# pcbNoJet.net
KiCad netlist of a schematic drawn in EAGLE
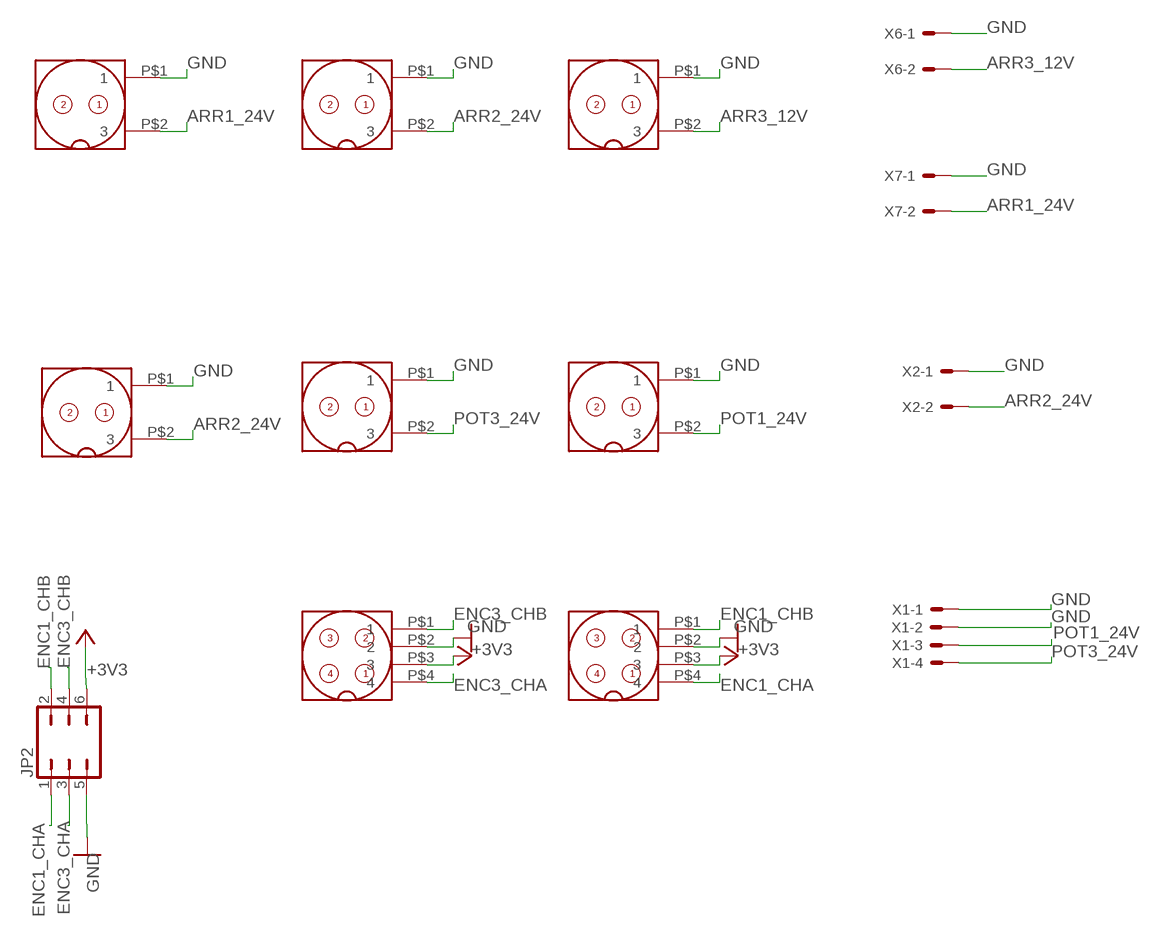
[diagram p0: schematic, sheet 1]

(export (version "E")
  (design (tool "Eeschema 10.0.6"))
  (components
    (comp (ref "JP2")
      (value "JP3Q")
      (footprint "eagle-import:JP3Q")
      (libsource (lib "eagle-import") (part "JP3Q"))
    )
    (comp (ref "U$1")
      (value "GX16_2_PINS")
      (footprint "eagle-import:GX16_2_PINS_PADS")
      (libsource (lib "eagle-import") (part "GX16_2_PINS"))
    )
    (comp (ref "U$2")
      (value "GX16_4_PINS")
      (footprint "eagle-import:GX16_4_PINS_PADS")
      (libsource (lib "eagle-import") (part "GX16_4_PINS"))
    )
    (comp (ref "U$3")
      (value "GX16_4_PINS")
      (footprint "eagle-import:GX16_4_PINS_PADS")
      (libsource (lib "eagle-import") (part "GX16_4_PINS"))
    )
    (comp (ref "U$4")
      (value "GX16_2_PINS")
      (footprint "eagle-import:GX16_2_PINS_PADS")
      (libsource (lib "eagle-import") (part "GX16_2_PINS"))
    )
    (comp (ref "U$5")
      (value "GX16_2_PINS")
      (footprint "eagle-import:GX16_2_PINS_PADS")
      (libsource (lib "eagle-import") (part "GX16_2_PINS"))
    )
    (comp (ref "U$6")
      (value "GX16_2_PINS")
      (footprint "eagle-import:GX16_2_PINS_PADS")
      (libsource (lib "eagle-import") (part "GX16_2_PINS"))
    )
    (comp (ref "U$8")
      (value "GX16_2_PINS")
      (footprint "eagle-import:GX16_2_PINS_PADS")
      (libsource (lib "eagle-import") (part "GX16_2_PINS"))
    )
    (comp (ref "U$9")
      (value "GX16_2_PINS")
      (footprint "eagle-import:GX16_2_PINS_PADS")
      (libsource (lib "eagle-import") (part "GX16_2_PINS"))
    )
    (comp (ref "X1")
      (value "5566-45569-4")
      (footprint "eagle-import:5569-4")
      (libsource (lib "eagle-import") (part "5566-45569-4"))
    )
    (comp (ref "X2")
      (value "5566-25569-2")
      (footprint "eagle-import:5569-2")
      (libsource (lib "eagle-import") (part "5566-25569-2"))
    )
    (comp (ref "X6")
      (value "5566-25569-2")
      (footprint "eagle-import:5569-2")
      (libsource (lib "eagle-import") (part "5566-25569-2"))
    )
    (comp (ref "X7")
      (value "5566-25569-2")
      (footprint "eagle-import:5569-2")
      (libsource (lib "eagle-import") (part "5566-25569-2"))
    )
  )
  (nets
    (net (code "1") (name "+3V3") (class "Default")
      (node (ref "JP2") (pin "6") (pinfunction "6_6") (pintype "passive"))
      (node (ref "U$2") (pin "P$3") (pinfunction "3_P$3") (pintype "bidirectional"))
      (node (ref "U$3") (pin "P$3") (pinfunction "3_P$3") (pintype "bidirectional"))
    )
    (net (code "2") (name "/ARR1_24V") (class "Default")
      (node (ref "U$4") (pin "P$2") (pinfunction "3_P$2") (pintype "bidirectional"))
      (node (ref "X7") (pin "2") (pinfunction "S_2") (pintype "passive"))
    )
    (net (code "3") (name "/ARR2_24V") (class "Default")
      (node (ref "U$1") (pin "P$2") (pinfunction "3_P$2") (pintype "bidirectional"))
      (node (ref "U$5") (pin "P$2") (pinfunction "3_P$2") (pintype "bidirectional"))
      (node (ref "X2") (pin "2") (pinfunction "S_2") (pintype "passive"))
    )
    (net (code "4") (name "/ARR3_12V") (class "Default")
      (node (ref "U$6") (pin "P$2") (pinfunction "3_P$2") (pintype "bidirectional"))
      (node (ref "X6") (pin "2") (pinfunction "S_2") (pintype "passive"))
    )
    (net (code "5") (name "/ENC1_CHA") (class "Default")
      (node (ref "JP2") (pin "1") (pinfunction "1_1") (pintype "passive"))
      (node (ref "U$3") (pin "P$4") (pinfunction "4_P$4") (pintype "bidirectional"))
    )
    (net (code "6") (name "/ENC1_CHB") (class "Default")
      (node (ref "JP2") (pin "2") (pinfunction "2_2") (pintype "passive"))
      (node (ref "U$3") (pin "P$1") (pinfunction "1_P$1") (pintype "bidirectional"))
    )
    (net (code "7") (name "/ENC3_CHA") (class "Default")
      (node (ref "JP2") (pin "3") (pinfunction "3_3") (pintype "passive"))
      (node (ref "U$2") (pin "P$4") (pinfunction "4_P$4") (pintype "bidirectional"))
    )
    (net (code "8") (name "/ENC3_CHB") (class "Default")
      (node (ref "JP2") (pin "4") (pinfunction "4_4") (pintype "passive"))
      (node (ref "U$2") (pin "P$1") (pinfunction "1_P$1") (pintype "bidirectional"))
    )
    (net (code "9") (name "/POT1_24V") (class "Default")
      (node (ref "U$9") (pin "P$2") (pinfunction "3_P$2") (pintype "bidirectional"))
      (node (ref "X1") (pin "3") (pinfunction "S_3") (pintype "passive"))
    )
    (net (code "10") (name "/POT3_24V") (class "Default")
      (node (ref "U$8") (pin "P$2") (pinfunction "3_P$2") (pintype "bidirectional"))
      (node (ref "X1") (pin "4") (pinfunction "S_4") (pintype "passive"))
    )
    (net (code "11") (name "GND") (class "Default")
      (node (ref "JP2") (pin "5") (pinfunction "5_5") (pintype "passive"))
      (node (ref "U$1") (pin "P$1") (pinfunction "1_P$1") (pintype "bidirectional"))
      (node (ref "U$2") (pin "P$2") (pinfunction "2_P$2") (pintype "bidirectional"))
      (node (ref "U$3") (pin "P$2") (pinfunction "2_P$2") (pintype "bidirectional"))
      (node (ref "U$4") (pin "P$1") (pinfunction "1_P$1") (pintype "bidirectional"))
      (node (ref "U$5") (pin "P$1") (pinfunction "1_P$1") (pintype "bidirectional"))
      (node (ref "U$6") (pin "P$1") (pinfunction "1_P$1") (pintype "bidirectional"))
      (node (ref "U$8") (pin "P$1") (pinfunction "1_P$1") (pintype "bidirectional"))
      (node (ref "U$9") (pin "P$1") (pinfunction "1_P$1") (pintype "bidirectional"))
      (node (ref "X1") (pin "1") (pinfunction "S_1") (pintype "passive"))
      (node (ref "X1") (pin "2") (pinfunction "S_2") (pintype "passive"))
      (node (ref "X2") (pin "1") (pinfunction "S_1") (pintype "passive"))
      (node (ref "X6") (pin "1") (pinfunction "S_1") (pintype "passive"))
      (node (ref "X7") (pin "1") (pinfunction "S_1") (pintype "passive"))
    )
  )
)
